# llrf_afe_pwr_single_ch.net
KiCad netlist of a schematic drawn in Altium Designer
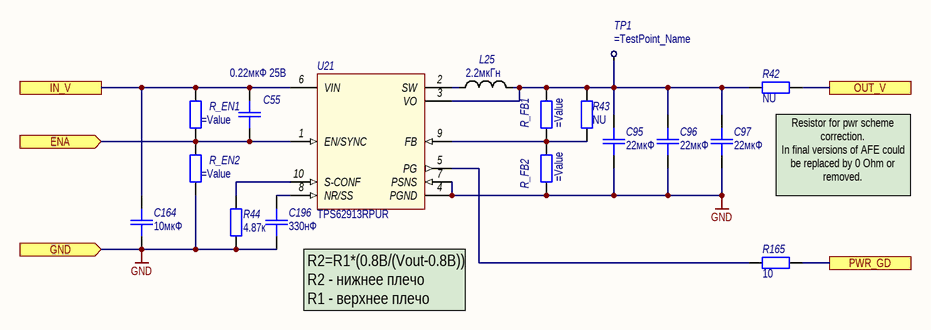
[diagram p0: llrf_afe_pwr_single_ch.SchDoc]

(export (version "E")
  (design (tool "Eeschema 10.0.6"))
  (components
    (comp (ref "C55")
      (value "0.22мкФ 25В")
      (footprint "SMD_C0603")
      (description "Capacitor")
      (libsource (lib "Passive") (part "Capacitor"))
    )
    (comp (ref "C95")
      (value "22мкФ")
      (footprint "SMD_C0805")
      (description "Capacitor")
      (libsource (lib "Passive") (part "Capacitor"))
    )
    (comp (ref "C96")
      (value "22мкФ")
      (footprint "SMD_C0805")
      (description "Capacitor")
      (libsource (lib "Passive") (part "Capacitor"))
    )
    (comp (ref "C97")
      (value "22мкФ")
      (footprint "SMD_C0805")
      (description "Capacitor")
      (libsource (lib "Passive") (part "Capacitor"))
    )
    (comp (ref "C164")
      (value "10мкФ")
      (footprint "SMD_C0805")
      (description "Capacitor")
      (libsource (lib "Passive") (part "Capacitor"))
    )
    (comp (ref "C196")
      (value "330нФ")
      (footprint "SMD_C0402")
      (description "Capacitor")
      (libsource (lib "Passive") (part "Capacitor"))
    )
    (comp (ref "L25")
      (value "2.2мкГн")
      (footprint "SMD_1210")
      (description "Inductor")
      (libsource (lib "Passive") (part "Inductor"))
    )
    (comp (ref "R42")
      (value "NU")
      (footprint "SMD_1206")
      (description "Resistor")
      (libsource (lib "") (part "Resistor_1"))
    )
    (comp (ref "R43")
      (value "NU")
      (footprint "SMD_0603")
      (description "Resistor")
      (libsource (lib "Passive") (part "Resistor"))
    )
    (comp (ref "R44")
      (value "4.87к")
      (footprint "SMD_0603")
      (description "Resistor")
      (libsource (lib "Passive") (part "Resistor"))
    )
    (comp (ref "R165")
      (value "10")
      (footprint "SMD_0603")
      (description "Resistor")
      (libsource (lib "") (part "Resistor_1"))
    )
    (comp (ref "R_EN1")
      (value "~")
      (footprint "SMD_0603")
      (description "Resistor")
      (libsource (lib "Passive") (part "Resistor"))
    )
    (comp (ref "R_EN2")
      (value "~")
      (footprint "SMD_0603")
      (description "Resistor")
      (libsource (lib "Passive") (part "Resistor"))
    )
    (comp (ref "R_FB1")
      (value "~")
      (footprint "SMD_0603")
      (description "Resistor")
      (libsource (lib "Passive") (part "Resistor"))
    )
    (comp (ref "R_FB2")
      (value "~")
      (footprint "SMD_0603")
      (description "Resistor")
      (libsource (lib "Passive") (part "Resistor"))
    )
    (comp (ref "TP1") (value "~") (footprint "TestPoint") (libsource (lib "Connector") (part "TP")))
    (comp (ref "U21")
      (value "TPS62913")
      (footprint "RPU0010A")
      (description "TPS62913 3-V to 17-V, 3-A Low Noise and Low Ripple Buck Converter")
      (fields (field (name "НАИМЕНОВАНИЕ") "TPS62913RPUR"))
      (libsource (lib "DC_DC") (part "TPS62913"))
    )
  )
  (nets
    (net (code "1") (name "/ENA") (class "Default")
      (node (ref "C55") (pin "1") (pinfunction "1_1") (pintype "passive"))
      (node (ref "R_EN1") (pin "1") (pinfunction "1_1") (pintype "passive"))
      (node (ref "R_EN2") (pin "2") (pinfunction "2_2") (pintype "passive"))
      (node (ref "U21") (pin "1") (pinfunction "EN/SYNC_1") (pintype "input"))
    )
    (net (code "2") (name "/IN_V") (class "Default")
      (node (ref "C164") (pin "2") (pinfunction "2_2") (pintype "passive"))
      (node (ref "C55") (pin "2") (pinfunction "2_2") (pintype "passive"))
      (node (ref "R_EN1") (pin "2") (pinfunction "2_2") (pintype "passive"))
      (node (ref "U21") (pin "6") (pinfunction "VIN_6") (pintype "power_in"))
    )
    (net (code "3") (name "/OUT_V") (class "Default")
      (node (ref "R42") (pin "1") (pinfunction "1_1") (pintype "passive"))
    )
    (net (code "4") (name "/PWR_GD") (class "Default")
      (node (ref "R165") (pin "1") (pinfunction "1_1") (pintype "passive"))
    )
    (net (code "5") (name "GND") (class "Default")
      (node (ref "C164") (pin "1") (pinfunction "1_1") (pintype "passive"))
      (node (ref "C196") (pin "1") (pinfunction "1_1") (pintype "passive"))
      (node (ref "C95") (pin "1") (pinfunction "1_1") (pintype "passive"))
      (node (ref "C96") (pin "1") (pinfunction "1_1") (pintype "passive"))
      (node (ref "C97") (pin "1") (pinfunction "1_1") (pintype "passive"))
      (node (ref "R44") (pin "1") (pinfunction "1_1") (pintype "passive"))
      (node (ref "R_EN2") (pin "1") (pinfunction "1_1") (pintype "passive"))
      (node (ref "R_FB2") (pin "1") (pinfunction "1_1") (pintype "passive"))
      (node (ref "U21") (pin "4") (pinfunction "PGND_4") (pintype "power_in"))
      (node (ref "U21") (pin "7") (pinfunction "PSNS_7") (pintype "input"))
    )
    (net (code "6") (name "Net-(TP1-TP)") (class "Default")
      (node (ref "C95") (pin "2") (pinfunction "2_2") (pintype "passive"))
      (node (ref "C96") (pin "2") (pinfunction "2_2") (pintype "passive"))
      (node (ref "C97") (pin "2") (pinfunction "2_2") (pintype "passive"))
      (node (ref "L25") (pin "2") (pinfunction "2_2") (pintype "passive"))
      (node (ref "R42") (pin "2") (pinfunction "2_2") (pintype "passive"))
      (node (ref "R43") (pin "2") (pinfunction "2_2") (pintype "passive"))
      (node (ref "R_FB1") (pin "2") (pinfunction "2_2") (pintype "passive"))
      (node (ref "TP1") (pin "0") (pinfunction "TP_0") (pintype "passive"))
      (node (ref "U21") (pin "3") (pinfunction "VO_3") (pintype "power_in"))
    )
    (net (code "7") (name "Net-(U21-FB)") (class "Default")
      (node (ref "R43") (pin "1") (pinfunction "1_1") (pintype "passive"))
      (node (ref "R_FB1") (pin "1") (pinfunction "1_1") (pintype "passive"))
      (node (ref "R_FB2") (pin "2") (pinfunction "2_2") (pintype "passive"))
      (node (ref "U21") (pin "9") (pinfunction "FB_9") (pintype "input"))
    )
    (net (code "8") (name "Net-(U21-NR{slash}SS)") (class "Default")
      (node (ref "C196") (pin "2") (pinfunction "2_2") (pintype "passive"))
      (node (ref "U21") (pin "8") (pinfunction "NR/SS_8") (pintype "input"))
    )
    (net (code "9") (name "Net-(U21-PG)") (class "Default")
      (node (ref "R165") (pin "2") (pinfunction "2_2") (pintype "passive"))
      (node (ref "U21") (pin "5") (pinfunction "PG_5") (pintype "output"))
    )
    (net (code "10") (name "Net-(U21-S-CONF)") (class "Default")
      (node (ref "R44") (pin "2") (pinfunction "2_2") (pintype "passive"))
      (node (ref "U21") (pin "10") (pinfunction "S-CONF_10") (pintype "input"))
    )
    (net (code "11") (name "Net-(U21-SW)") (class "Default")
      (node (ref "L25") (pin "1") (pinfunction "1_1") (pintype "passive"))
      (node (ref "U21") (pin "2") (pinfunction "SW_2") (pintype "power_in"))
    )
  )
)
